# banana-split.net
KiCad netlist of a schematic drawn in EAGLE
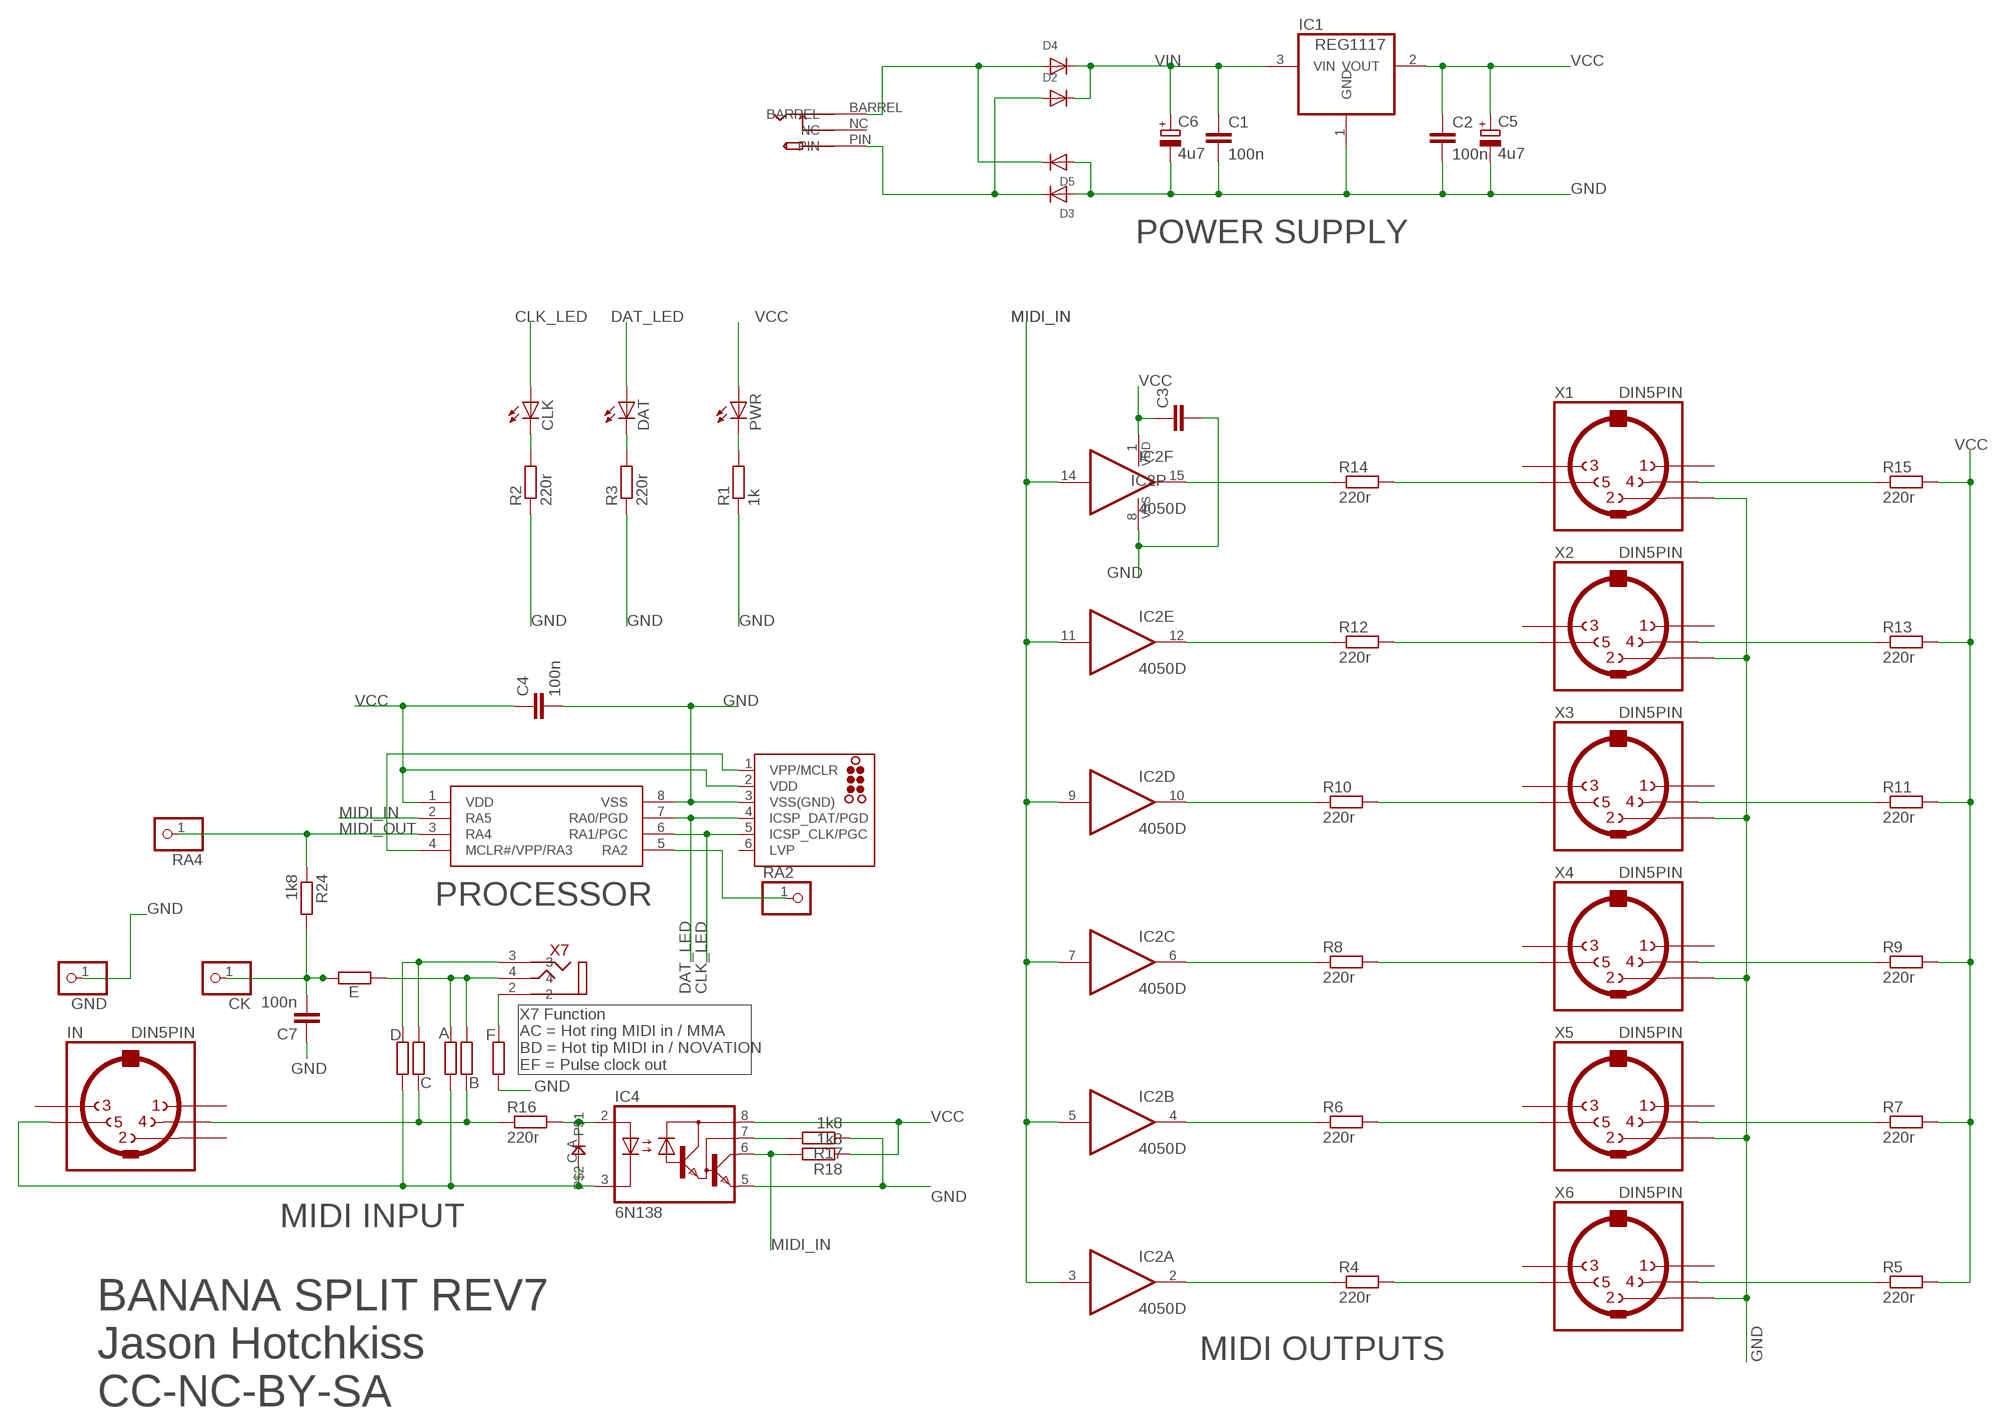
[diagram p0: schematic, sheet 1]

(export (version "E")
  (design (tool "Eeschema 10.0.6"))
  (components
    (comp (ref "A")
      (value "1k8")
      (footprint "eagle-import:R0805")
      (libsource (lib "eagle-import") (part "R-EU_R0805"))
    )
    (comp (ref "B")
      (value "1k8")
      (footprint "eagle-import:R0805")
      (libsource (lib "eagle-import") (part "R-EU_R0805"))
    )
    (comp (ref "C")
      (value "1k8")
      (footprint "eagle-import:R0805")
      (libsource (lib "eagle-import") (part "R-EU_R0805"))
    )
    (comp (ref "C1")
      (value "100n")
      (footprint "eagle-import:C0805")
      (libsource (lib "eagle-import") (part "C-EUC0805"))
    )
    (comp (ref "C2")
      (value "100n")
      (footprint "eagle-import:C0805")
      (libsource (lib "eagle-import") (part "C-EUC0805"))
    )
    (comp (ref "C3")
      (value "C-EUC0805")
      (footprint "eagle-import:C0805")
      (libsource (lib "eagle-import") (part "C-EUC0805"))
    )
    (comp (ref "C4")
      (value "100n")
      (footprint "eagle-import:C0805")
      (libsource (lib "eagle-import") (part "C-EUC0805"))
    )
    (comp (ref "C5")
      (value "4u7")
      (footprint "eagle-import:E2-4")
      (libsource (lib "eagle-import") (part "CPOL-EUE2-4"))
    )
    (comp (ref "C6")
      (value "4u7")
      (footprint "eagle-import:E2-4")
      (libsource (lib "eagle-import") (part "CPOL-EUE2-4"))
    )
    (comp (ref "C7")
      (value "100n")
      (footprint "eagle-import:C0805")
      (libsource (lib "eagle-import") (part "C-EUC0805"))
    )
    (comp (ref "CK")
      (value "PINHD-1X1")
      (footprint "eagle-import:1X01")
      (libsource (lib "eagle-import") (part "PINHD-1X1"))
    )
    (comp (ref "CLK")
      (value "LED3MM")
      (footprint "eagle-import:LED3MM")
      (libsource (lib "eagle-import") (part "LED3MM"))
    )
    (comp (ref "D")
      (value "1k8")
      (footprint "eagle-import:R0805")
      (libsource (lib "eagle-import") (part "R-EU_R0805"))
    )
    (comp (ref "D1")
      (value "0805DIODE")
      (footprint "eagle-import:0805DIODE")
      (libsource (lib "eagle-import") (part "0805DIODE"))
    )
    (comp (ref "D2")
      (value "DIODESOD-123")
      (footprint "eagle-import:SOD-123")
      (libsource (lib "eagle-import") (part "DIODESOD-123"))
    )
    (comp (ref "D3")
      (value "DIODESOD-123")
      (footprint "eagle-import:SOD-123")
      (libsource (lib "eagle-import") (part "DIODESOD-123"))
    )
    (comp (ref "D4")
      (value "DIODESOD-123")
      (footprint "eagle-import:SOD-123")
      (libsource (lib "eagle-import") (part "DIODESOD-123"))
    )
    (comp (ref "D5")
      (value "DIODESOD-123")
      (footprint "eagle-import:SOD-123")
      (libsource (lib "eagle-import") (part "DIODESOD-123"))
    )
    (comp (ref "DAT")
      (value "LED3MM")
      (footprint "eagle-import:LED3MM")
      (libsource (lib "eagle-import") (part "LED3MM"))
    )
    (comp (ref "E")
      (value "1k8")
      (footprint "eagle-import:R0805")
      (libsource (lib "eagle-import") (part "R-EU_R0805"))
    )
    (comp (ref "F")
      (value "1k8")
      (footprint "eagle-import:R0805")
      (libsource (lib "eagle-import") (part "R-EU_R0805"))
    )
    (comp (ref "GND")
      (value "PINHD-1X1")
      (footprint "eagle-import:1X01")
      (libsource (lib "eagle-import") (part "PINHD-1X1"))
    )
    (comp (ref "IC1")
      (value "REG1117")
      (footprint "eagle-import:SOT223")
      (libsource (lib "eagle-import") (part "REG1117"))
    )
    (comp (ref "IC2")
      (value "4050D")
      (footprint "eagle-import:SO16")
      (libsource (lib "eagle-import") (part "4050D"))
    )
    (comp (ref "IC3")
      (value "PIC12F1822SO08")
      (footprint "eagle-import:SO08")
      (libsource (lib "eagle-import") (part "PIC12F1822SO08"))
    )
    (comp (ref "IC4")
      (value "6N138")
      (footprint "eagle-import:DIL08")
      (fields (field (name "MF") "VISHAY/TELEFUNKEN"))
      (libsource (lib "eagle-import") (part "6N138"))
    )
    (comp (ref "ICSP")
      (value "TC2030-MCP-NL")
      (footprint "eagle-import:TC2030-MCP-NL")
      (libsource (lib "eagle-import") (part "TC2030-MCP-NL"))
    )
    (comp (ref "IN")
      (value "DIN5PIN")
      (footprint "eagle-import:EDGEDIN")
      (libsource (lib "eagle-import") (part "DIN5PIN"))
    )
    (comp (ref "PWR")
      (value "LED3MM")
      (footprint "eagle-import:LED3MM")
      (libsource (lib "eagle-import") (part "LED3MM"))
    )
    (comp (ref "R1")
      (value "1k")
      (footprint "eagle-import:R0805")
      (libsource (lib "eagle-import") (part "R-EU_R0805"))
    )
    (comp (ref "R2")
      (value "220r")
      (footprint "eagle-import:R0805")
      (libsource (lib "eagle-import") (part "R-EU_R0805"))
    )
    (comp (ref "R3")
      (value "220r")
      (footprint "eagle-import:R0805")
      (libsource (lib "eagle-import") (part "R-EU_R0805"))
    )
    (comp (ref "R4")
      (value "220r")
      (footprint "eagle-import:R0805")
      (libsource (lib "eagle-import") (part "R-EU_R0805"))
    )
    (comp (ref "R5")
      (value "220r")
      (footprint "eagle-import:R0805")
      (libsource (lib "eagle-import") (part "R-EU_R0805"))
    )
    (comp (ref "R6")
      (value "220r")
      (footprint "eagle-import:R0805")
      (libsource (lib "eagle-import") (part "R-EU_R0805"))
    )
    (comp (ref "R7")
      (value "220r")
      (footprint "eagle-import:R0805")
      (libsource (lib "eagle-import") (part "R-EU_R0805"))
    )
    (comp (ref "R8")
      (value "220r")
      (footprint "eagle-import:R0805")
      (libsource (lib "eagle-import") (part "R-EU_R0805"))
    )
    (comp (ref "R9")
      (value "220r")
      (footprint "eagle-import:R0805")
      (libsource (lib "eagle-import") (part "R-EU_R0805"))
    )
    (comp (ref "R10")
      (value "220r")
      (footprint "eagle-import:R0805")
      (libsource (lib "eagle-import") (part "R-EU_R0805"))
    )
    (comp (ref "R11")
      (value "220r")
      (footprint "eagle-import:R0805")
      (libsource (lib "eagle-import") (part "R-EU_R0805"))
    )
    (comp (ref "R12")
      (value "220r")
      (footprint "eagle-import:R0805")
      (libsource (lib "eagle-import") (part "R-EU_R0805"))
    )
    (comp (ref "R13")
      (value "220r")
      (footprint "eagle-import:R0805")
      (libsource (lib "eagle-import") (part "R-EU_R0805"))
    )
    (comp (ref "R14")
      (value "220r")
      (footprint "eagle-import:R0805")
      (libsource (lib "eagle-import") (part "R-EU_R0805"))
    )
    (comp (ref "R15")
      (value "220r")
      (footprint "eagle-import:R0805")
      (libsource (lib "eagle-import") (part "R-EU_R0805"))
    )
    (comp (ref "R16")
      (value "220r")
      (footprint "eagle-import:R0805")
      (libsource (lib "eagle-import") (part "R-EU_R0805"))
    )
    (comp (ref "R17")
      (value "1k8")
      (footprint "eagle-import:R0805")
      (libsource (lib "eagle-import") (part "R-EU_R0805"))
    )
    (comp (ref "R18")
      (value "1k8")
      (footprint "eagle-import:R0805")
      (libsource (lib "eagle-import") (part "R-EU_R0805"))
    )
    (comp (ref "R24")
      (value "1k8")
      (footprint "eagle-import:R0805")
      (libsource (lib "eagle-import") (part "R-EU_R0805"))
    )
    (comp (ref "RA2")
      (value "PINHD-1X1")
      (footprint "eagle-import:1X01")
      (libsource (lib "eagle-import") (part "PINHD-1X1"))
    )
    (comp (ref "RA4")
      (value "PINHD-1X1")
      (footprint "eagle-import:1X01")
      (libsource (lib "eagle-import") (part "PINHD-1X1"))
    )
    (comp (ref "U$1")
      (value "PWR_SOCKET_2_1MM")
      (footprint "eagle-import:PWR_SOCKET_2_1MM")
      (libsource (lib "eagle-import") (part "PWR_SOCKET_2_1MM"))
    )
    (comp (ref "X1")
      (value "DIN5PIN")
      (footprint "eagle-import:EDGEDIN")
      (libsource (lib "eagle-import") (part "DIN5PIN"))
    )
    (comp (ref "X2")
      (value "DIN5PIN")
      (footprint "eagle-import:EDGEDIN")
      (libsource (lib "eagle-import") (part "DIN5PIN"))
    )
    (comp (ref "X3")
      (value "DIN5PIN")
      (footprint "eagle-import:EDGEDIN")
      (libsource (lib "eagle-import") (part "DIN5PIN"))
    )
    (comp (ref "X4")
      (value "DIN5PIN")
      (footprint "eagle-import:EDGEDIN")
      (libsource (lib "eagle-import") (part "DIN5PIN"))
    )
    (comp (ref "X5")
      (value "DIN5PIN")
      (footprint "eagle-import:EDGEDIN")
      (libsource (lib "eagle-import") (part "DIN5PIN"))
    )
    (comp (ref "X6")
      (value "DIN5PIN")
      (footprint "eagle-import:EDGEDIN")
      (libsource (lib "eagle-import") (part "DIN5PIN"))
    )
    (comp (ref "X7")
      (value "VERTICAL_3_5MM_SOCKET")
      (footprint "eagle-import:VERTICAL_3_5MM_SOCKET")
      (libsource (lib "eagle-import") (part "VERTICAL_3_5MM_SOCKET"))
    )
  )
  (nets
    (net (code "1") (name "/CLK_LED") (class "Default")
      (node (ref "CLK") (pin "A") (pinfunction "A_A") (pintype "passive"))
      (node (ref "IC3") (pin "6") (pinfunction "RA1/PGC_6") (pintype "bidirectional"))
      (node (ref "ICSP") (pin "5") (pinfunction "ICSP_CLK/PGC_5") (pintype "output"))
    )
    (net (code "2") (name "/DAT_LED") (class "Default")
      (node (ref "DAT") (pin "A") (pinfunction "A_A") (pintype "passive"))
      (node (ref "IC3") (pin "7") (pinfunction "RA0/PGD_7") (pintype "bidirectional"))
      (node (ref "ICSP") (pin "4") (pinfunction "ICSP_DAT/PGD_4") (pintype "bidirectional"))
    )
    (net (code "3") (name "/GND") (class "Default")
      (node (ref "C1") (pin "2") (pinfunction "2_2") (pintype "passive"))
      (node (ref "C2") (pin "2") (pinfunction "2_2") (pintype "passive"))
      (node (ref "C3") (pin "2") (pinfunction "2_2") (pintype "passive"))
      (node (ref "C4") (pin "2") (pinfunction "2_2") (pintype "passive"))
      (node (ref "C5") (pin "-") (pinfunction "-_-") (pintype "passive"))
      (node (ref "C6") (pin "-") (pinfunction "-_-") (pintype "passive"))
      (node (ref "C7") (pin "1") (pinfunction "1_1") (pintype "passive"))
      (node (ref "D3") (pin "A") (pinfunction "A_A") (pintype "passive"))
      (node (ref "D5") (pin "A") (pinfunction "A_A") (pintype "passive"))
      (node (ref "F") (pin "1") (pinfunction "1_1") (pintype "passive"))
      (node (ref "GND") (pin "1") (pinfunction "1_1") (pintype "passive"))
      (node (ref "IC1") (pin "1") (pinfunction "GND_1") (pintype "power_in"))
      (node (ref "IC2") (pin "8") (pinfunction "VSS_8") (pintype "power_in"))
      (node (ref "IC3") (pin "8") (pinfunction "VSS_8") (pintype "power_in"))
      (node (ref "IC4") (pin "5") (pinfunction "GND_5") (pintype "passive"))
      (node (ref "ICSP") (pin "3") (pinfunction "VSS(GND)_3") (pintype "power_in"))
      (node (ref "R1") (pin "1") (pinfunction "1_1") (pintype "passive"))
      (node (ref "R17") (pin "1") (pinfunction "1_1") (pintype "passive"))
      (node (ref "R2") (pin "1") (pinfunction "1_1") (pintype "passive"))
      (node (ref "R3") (pin "1") (pinfunction "1_1") (pintype "passive"))
      (node (ref "X1") (pin "2") (pinfunction "2_2") (pintype "passive"))
      (node (ref "X2") (pin "2") (pinfunction "2_2") (pintype "passive"))
      (node (ref "X3") (pin "2") (pinfunction "2_2") (pintype "passive"))
      (node (ref "X4") (pin "2") (pinfunction "2_2") (pintype "passive"))
      (node (ref "X5") (pin "2") (pinfunction "2_2") (pintype "passive"))
      (node (ref "X6") (pin "2") (pinfunction "2_2") (pintype "passive"))
    )
    (net (code "4") (name "/MIDI_IN") (class "Default")
      (node (ref "IC2") (pin "11") (pinfunction "I_11") (pintype "input"))
      (node (ref "IC2") (pin "14") (pinfunction "I_14") (pintype "input"))
      (node (ref "IC2") (pin "3") (pinfunction "I_3") (pintype "input"))
      (node (ref "IC2") (pin "5") (pinfunction "I_5") (pintype "input"))
      (node (ref "IC2") (pin "7") (pinfunction "I_7") (pintype "input"))
      (node (ref "IC2") (pin "9") (pinfunction "I_9") (pintype "input"))
      (node (ref "IC3") (pin "2") (pinfunction "RA5_2") (pintype "bidirectional"))
      (node (ref "IC4") (pin "6") (pinfunction "VO_6") (pintype "passive"))
      (node (ref "R18") (pin "2") (pinfunction "2_2") (pintype "passive"))
    )
    (net (code "5") (name "/MIDI_OUT") (class "Default")
      (node (ref "IC3") (pin "3") (pinfunction "RA4_3") (pintype "bidirectional"))
      (node (ref "R24") (pin "1") (pinfunction "1_1") (pintype "passive"))
      (node (ref "RA4") (pin "1") (pinfunction "1_1") (pintype "passive"))
    )
    (net (code "6") (name "/VCC") (class "Default")
      (node (ref "C2") (pin "1") (pinfunction "1_1") (pintype "passive"))
      (node (ref "C3") (pin "1") (pinfunction "1_1") (pintype "passive"))
      (node (ref "C4") (pin "1") (pinfunction "1_1") (pintype "passive"))
      (node (ref "C5") (pin "+") (pinfunction "+_+") (pintype "passive"))
      (node (ref "IC1") (pin "2") (pinfunction "VOUT_2") (pintype "output"))
      (node (ref "IC2") (pin "1") (pinfunction "VDD_1") (pintype "power_in"))
      (node (ref "IC3") (pin "1") (pinfunction "VDD_1") (pintype "power_in"))
      (node (ref "IC4") (pin "8") (pinfunction "VCC_8") (pintype "passive"))
      (node (ref "ICSP") (pin "2") (pinfunction "VDD_2") (pintype "power_in"))
      (node (ref "PWR") (pin "A") (pinfunction "A_A") (pintype "passive"))
      (node (ref "R11") (pin "2") (pinfunction "2_2") (pintype "passive"))
      (node (ref "R13") (pin "2") (pinfunction "2_2") (pintype "passive"))
      (node (ref "R15") (pin "2") (pinfunction "2_2") (pintype "passive"))
      (node (ref "R18") (pin "1") (pinfunction "1_1") (pintype "passive"))
      (node (ref "R5") (pin "2") (pinfunction "2_2") (pintype "passive"))
      (node (ref "R7") (pin "2") (pinfunction "2_2") (pintype "passive"))
      (node (ref "R9") (pin "2") (pinfunction "2_2") (pintype "passive"))
    )
    (net (code "7") (name "/VIN") (class "Default")
      (node (ref "C1") (pin "1") (pinfunction "1_1") (pintype "passive"))
      (node (ref "C6") (pin "+") (pinfunction "+_+") (pintype "passive"))
      (node (ref "D2") (pin "C") (pinfunction "C_C") (pintype "passive"))
      (node (ref "D4") (pin "C") (pinfunction "C_C") (pintype "passive"))
      (node (ref "IC1") (pin "3") (pinfunction "VIN_3") (pintype "input"))
    )
    (net (code "8") (name "Net-(A-Pad2)") (class "Default")
      (node (ref "A") (pin "2") (pinfunction "2_2") (pintype "passive"))
      (node (ref "B") (pin "2") (pinfunction "2_2") (pintype "passive"))
      (node (ref "E") (pin "2") (pinfunction "2_2") (pintype "passive"))
      (node (ref "X7") (pin "4") (pinfunction "4_4") (pintype "bidirectional"))
    )
    (net (code "9") (name "Net-(B-Pad1)") (class "Default")
      (node (ref "B") (pin "1") (pinfunction "1_1") (pintype "passive"))
      (node (ref "C") (pin "1") (pinfunction "1_1") (pintype "passive"))
      (node (ref "IN") (pin "4") (pinfunction "4_4") (pintype "passive"))
      (node (ref "R16") (pin "1") (pinfunction "1_1") (pintype "passive"))
    )
    (net (code "10") (name "Net-(C-Pad2)") (class "Default")
      (node (ref "C") (pin "2") (pinfunction "2_2") (pintype "passive"))
      (node (ref "D") (pin "2") (pinfunction "2_2") (pintype "passive"))
      (node (ref "X7") (pin "3") (pinfunction "3_3") (pintype "bidirectional"))
    )
    (net (code "11") (name "Net-(C7-Pad2)") (class "Default")
      (node (ref "C7") (pin "2") (pinfunction "2_2") (pintype "passive"))
      (node (ref "CK") (pin "1") (pinfunction "1_1") (pintype "passive"))
      (node (ref "E") (pin "1") (pinfunction "1_1") (pintype "passive"))
      (node (ref "R24") (pin "2") (pinfunction "2_2") (pintype "passive"))
    )
    (net (code "12") (name "Net-(CLK-C)") (class "Default")
      (node (ref "CLK") (pin "K") (pinfunction "C_K") (pintype "passive"))
      (node (ref "R2") (pin "2") (pinfunction "2_2") (pintype "passive"))
    )
    (net (code "13") (name "Net-(D1-P$1)") (class "Default")
      (node (ref "A") (pin "1") (pinfunction "1_1") (pintype "passive"))
      (node (ref "D") (pin "1") (pinfunction "1_1") (pintype "passive"))
      (node (ref "D1") (pin "C") (pinfunction "P$1_C") (pintype "bidirectional"))
      (node (ref "IC4") (pin "3") (pinfunction "C_3") (pintype "passive"))
      (node (ref "IN") (pin "5") (pinfunction "5_5") (pintype "passive"))
    )
    (net (code "14") (name "Net-(D1-P$2)") (class "Default")
      (node (ref "D1") (pin "A") (pinfunction "P$2_A") (pintype "bidirectional"))
      (node (ref "IC4") (pin "2") (pinfunction "A_2") (pintype "passive"))
      (node (ref "R16") (pin "2") (pinfunction "2_2") (pintype "passive"))
    )
    (net (code "15") (name "Net-(D2-PadA)") (class "Default")
      (node (ref "D2") (pin "A") (pinfunction "A_A") (pintype "passive"))
      (node (ref "D3") (pin "C") (pinfunction "C_C") (pintype "passive"))
      (node (ref "U$1") (pin "PIN") (pinfunction "PIN_PIN") (pintype "bidirectional"))
    )
    (net (code "16") (name "Net-(D4-PadA)") (class "Default")
      (node (ref "D4") (pin "A") (pinfunction "A_A") (pintype "passive"))
      (node (ref "D5") (pin "C") (pinfunction "C_C") (pintype "passive"))
      (node (ref "U$1") (pin "BARREL") (pinfunction "BARREL_BARREL") (pintype "bidirectional"))
    )
    (net (code "17") (name "Net-(DAT-C)") (class "Default")
      (node (ref "DAT") (pin "K") (pinfunction "C_K") (pintype "passive"))
      (node (ref "R3") (pin "2") (pinfunction "2_2") (pintype "passive"))
    )
    (net (code "18") (name "Net-(F-Pad2)") (class "Default")
      (node (ref "F") (pin "2") (pinfunction "2_2") (pintype "passive"))
      (node (ref "X7") (pin "2") (pinfunction "2_2") (pintype "bidirectional"))
    )
    (net (code "19") (name "Net-(IC2A-O)") (class "Default")
      (node (ref "IC2") (pin "2") (pinfunction "O_2") (pintype "output"))
      (node (ref "R4") (pin "1") (pinfunction "1_1") (pintype "passive"))
    )
    (net (code "20") (name "Net-(IC2B-O)") (class "Default")
      (node (ref "IC2") (pin "4") (pinfunction "O_4") (pintype "output"))
      (node (ref "R6") (pin "1") (pinfunction "1_1") (pintype "passive"))
    )
    (net (code "21") (name "Net-(IC2C-O)") (class "Default")
      (node (ref "IC2") (pin "6") (pinfunction "O_6") (pintype "output"))
      (node (ref "R8") (pin "1") (pinfunction "1_1") (pintype "passive"))
    )
    (net (code "22") (name "Net-(IC2D-O)") (class "Default")
      (node (ref "IC2") (pin "10") (pinfunction "O_10") (pintype "output"))
      (node (ref "R10") (pin "1") (pinfunction "1_1") (pintype "passive"))
    )
    (net (code "23") (name "Net-(IC2E-O)") (class "Default")
      (node (ref "IC2") (pin "12") (pinfunction "O_12") (pintype "output"))
      (node (ref "R12") (pin "1") (pinfunction "1_1") (pintype "passive"))
    )
    (net (code "24") (name "Net-(IC2F-O)") (class "Default")
      (node (ref "IC2") (pin "15") (pinfunction "O_15") (pintype "output"))
      (node (ref "R14") (pin "1") (pinfunction "1_1") (pintype "passive"))
    )
    (net (code "25") (name "Net-(IC3-MCLR#{slash}VPP{slash}RA3)") (class "Default")
      (node (ref "IC3") (pin "4") (pinfunction "MCLR#/VPP/RA3_4") (pintype "bidirectional"))
      (node (ref "ICSP") (pin "1") (pinfunction "VPP/MCLR_1") (pintype "passive"))
    )
    (net (code "26") (name "Net-(IC3-RA2)") (class "Default")
      (node (ref "IC3") (pin "5") (pinfunction "RA2_5") (pintype "bidirectional"))
      (node (ref "RA2") (pin "1") (pinfunction "1_1") (pintype "passive"))
    )
    (net (code "27") (name "Net-(IC4-VB)") (class "Default")
      (node (ref "IC4") (pin "7") (pinfunction "VB_7") (pintype "passive"))
      (node (ref "R17") (pin "2") (pinfunction "2_2") (pintype "passive"))
    )
    (net (code "28") (name "Net-(PWR-C)") (class "Default")
      (node (ref "PWR") (pin "K") (pinfunction "C_K") (pintype "passive"))
      (node (ref "R1") (pin "2") (pinfunction "2_2") (pintype "passive"))
    )
    (net (code "29") (name "Net-(R4-Pad2)") (class "Default")
      (node (ref "R4") (pin "2") (pinfunction "2_2") (pintype "passive"))
      (node (ref "X6") (pin "5") (pinfunction "5_5") (pintype "passive"))
    )
    (net (code "30") (name "Net-(R5-Pad1)") (class "Default")
      (node (ref "R5") (pin "1") (pinfunction "1_1") (pintype "passive"))
      (node (ref "X6") (pin "4") (pinfunction "4_4") (pintype "passive"))
    )
    (net (code "31") (name "Net-(R6-Pad2)") (class "Default")
      (node (ref "R6") (pin "2") (pinfunction "2_2") (pintype "passive"))
      (node (ref "X5") (pin "5") (pinfunction "5_5") (pintype "passive"))
    )
    (net (code "32") (name "Net-(R7-Pad1)") (class "Default")
      (node (ref "R7") (pin "1") (pinfunction "1_1") (pintype "passive"))
      (node (ref "X5") (pin "4") (pinfunction "4_4") (pintype "passive"))
    )
    (net (code "33") (name "Net-(R8-Pad2)") (class "Default")
      (node (ref "R8") (pin "2") (pinfunction "2_2") (pintype "passive"))
      (node (ref "X4") (pin "5") (pinfunction "5_5") (pintype "passive"))
    )
    (net (code "34") (name "Net-(R9-Pad1)") (class "Default")
      (node (ref "R9") (pin "1") (pinfunction "1_1") (pintype "passive"))
      (node (ref "X4") (pin "4") (pinfunction "4_4") (pintype "passive"))
    )
    (net (code "35") (name "Net-(R10-Pad2)") (class "Default")
      (node (ref "R10") (pin "2") (pinfunction "2_2") (pintype "passive"))
      (node (ref "X3") (pin "5") (pinfunction "5_5") (pintype "passive"))
    )
    (net (code "36") (name "Net-(R11-Pad1)") (class "Default")
      (node (ref "R11") (pin "1") (pinfunction "1_1") (pintype "passive"))
      (node (ref "X3") (pin "4") (pinfunction "4_4") (pintype "passive"))
    )
    (net (code "37") (name "Net-(R12-Pad2)") (class "Default")
      (node (ref "R12") (pin "2") (pinfunction "2_2") (pintype "passive"))
      (node (ref "X2") (pin "5") (pinfunction "5_5") (pintype "passive"))
    )
    (net (code "38") (name "Net-(R13-Pad1)") (class "Default")
      (node (ref "R13") (pin "1") (pinfunction "1_1") (pintype "passive"))
      (node (ref "X2") (pin "4") (pinfunction "4_4") (pintype "passive"))
    )
    (net (code "39") (name "Net-(R14-Pad2)") (class "Default")
      (node (ref "R14") (pin "2") (pinfunction "2_2") (pintype "passive"))
      (node (ref "X1") (pin "5") (pinfunction "5_5") (pintype "passive"))
    )
    (net (code "40") (name "Net-(R15-Pad1)") (class "Default")
      (node (ref "R15") (pin "1") (pinfunction "1_1") (pintype "passive"))
      (node (ref "X1") (pin "4") (pinfunction "4_4") (pintype "passive"))
    )
    (net (code "41") (name "unconnected-(ICSP-LVP-Pad6)") (class "Default")
      (node (ref "ICSP") (pin "6") (pinfunction "LVP_6") (pintype "bidirectional"))
    )
    (net (code "42") (name "unconnected-(IN-Pad1)") (class "Default")
      (node (ref "IN") (pin "1") (pinfunction "1_1") (pintype "passive"))
    )
    (net (code "43") (name "unconnected-(IN-Pad2)") (class "Default")
      (node (ref "IN") (pin "2") (pinfunction "2_2") (pintype "passive"))
    )
    (net (code "44") (name "unconnected-(IN-Pad3)") (class "Default")
      (node (ref "IN") (pin "3") (pinfunction "3_3") (pintype "passive"))
    )
    (net (code "45") (name "unconnected-(U$1-PadNC)") (class "Default")
      (node (ref "U$1") (pin "NC") (pinfunction "NC_NC") (pintype "bidirectional"))
    )
    (net (code "46") (name "unconnected-(X1-Pad1)") (class "Default")
      (node (ref "X1") (pin "1") (pinfunction "1_1") (pintype "passive"))
    )
    (net (code "47") (name "unconnected-(X1-Pad3)") (class "Default")
      (node (ref "X1") (pin "3") (pinfunction "3_3") (pintype "passive"))
    )
    (net (code "48") (name "unconnected-(X2-Pad1)") (class "Default")
      (node (ref "X2") (pin "1") (pinfunction "1_1") (pintype "passive"))
    )
    (net (code "49") (name "unconnected-(X2-Pad3)") (class "Default")
      (node (ref "X2") (pin "3") (pinfunction "3_3") (pintype "passive"))
    )
    (net (code "50") (name "unconnected-(X3-Pad1)") (class "Default")
      (node (ref "X3") (pin "1") (pinfunction "1_1") (pintype "passive"))
    )
    (net (code "51") (name "unconnected-(X3-Pad3)") (class "Default")
      (node (ref "X3") (pin "3") (pinfunction "3_3") (pintype "passive"))
    )
    (net (code "52") (name "unconnected-(X4-Pad1)") (class "Default")
      (node (ref "X4") (pin "1") (pinfunction "1_1") (pintype "passive"))
    )
    (net (code "53") (name "unconnected-(X4-Pad3)") (class "Default")
      (node (ref "X4") (pin "3") (pinfunction "3_3") (pintype "passive"))
    )
    (net (code "54") (name "unconnected-(X5-Pad1)") (class "Default")
      (node (ref "X5") (pin "1") (pinfunction "1_1") (pintype "passive"))
    )
    (net (code "55") (name "unconnected-(X5-Pad3)") (class "Default")
      (node (ref "X5") (pin "3") (pinfunction "3_3") (pintype "passive"))
    )
    (net (code "56") (name "unconnected-(X6-Pad1)") (class "Default")
      (node (ref "X6") (pin "1") (pinfunction "1_1") (pintype "passive"))
    )
    (net (code "57") (name "unconnected-(X6-Pad3)") (class "Default")
      (node (ref "X6") (pin "3") (pinfunction "3_3") (pintype "passive"))
    )
  )
)
